# vcf-lm324-stereo.net
KiCad netlist of a schematic drawn in EAGLE
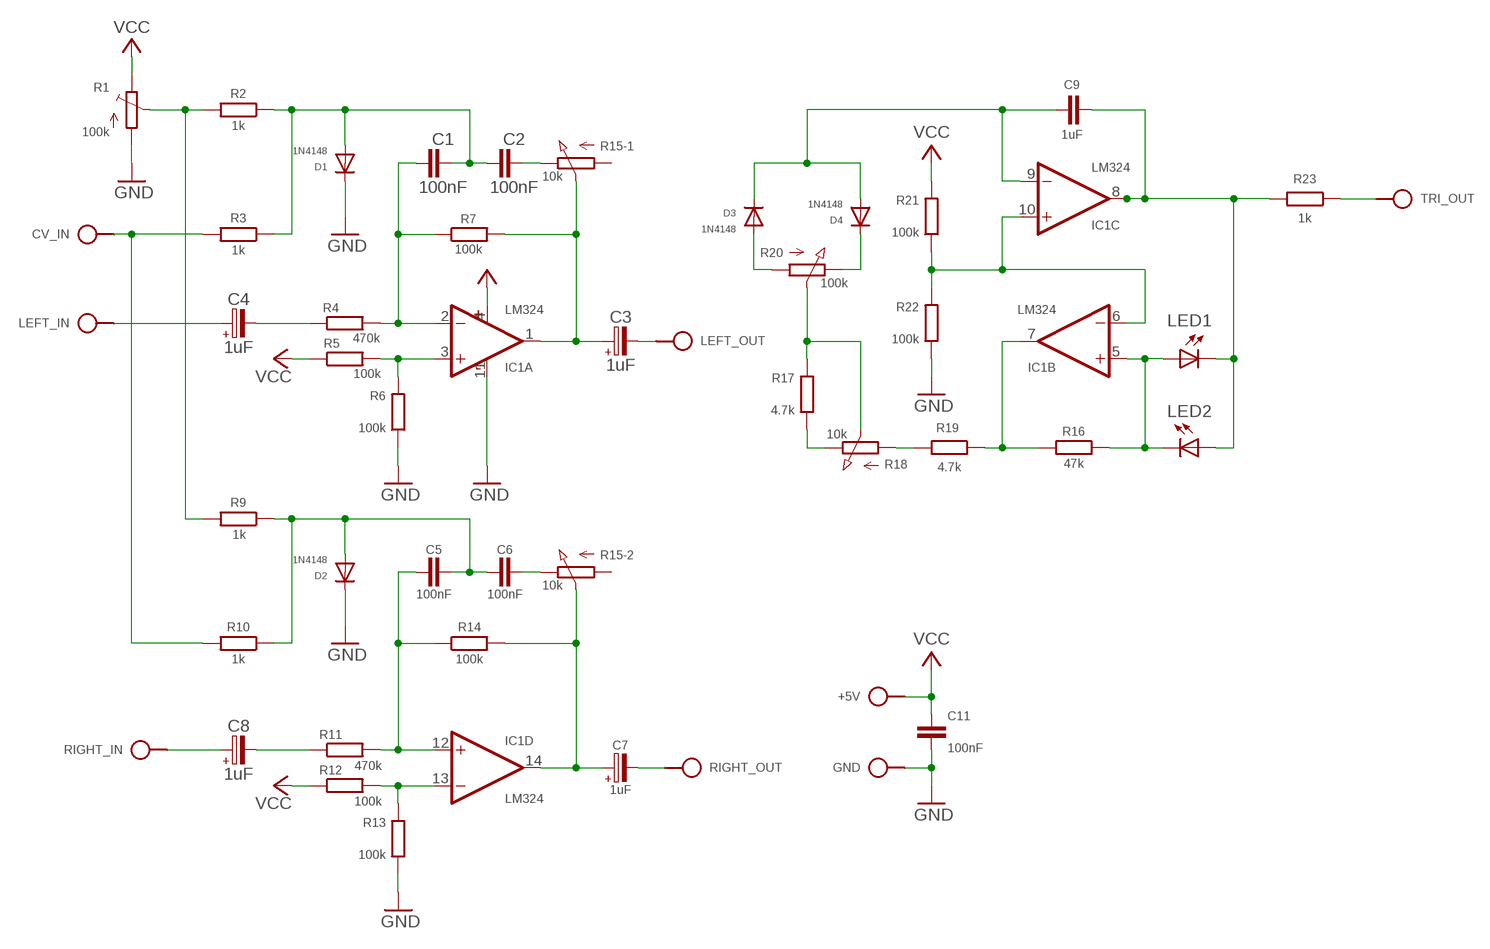
[diagram p0: schematic, sheet 1]

(export (version "E")
  (design (tool "Eeschema 10.0.6"))
  (components
    (comp (ref "+5V")
      (value "VCC")
      (footprint "eagle-import:SPAD")
      (libsource (lib "eagle-import") (part "SPAD"))
    )
    (comp (ref "C1")
      (value "100nF")
      (footprint "eagle-import:C050-024X044")
      (libsource (lib "eagle-import") (part "C050-024X044"))
    )
    (comp (ref "C2")
      (value "100nF")
      (footprint "eagle-import:C050-024X044")
      (libsource (lib "eagle-import") (part "C050-024X044"))
    )
    (comp (ref "C3")
      (value "1uF")
      (footprint "eagle-import:E2,5-3")
      (libsource (lib "eagle-import") (part "CPOLE2,5-3"))
    )
    (comp (ref "C4")
      (value "1uF")
      (footprint "eagle-import:E2,5-3")
      (libsource (lib "eagle-import") (part "CPOLE2,5-3"))
    )
    (comp (ref "C5")
      (value "100nF")
      (footprint "eagle-import:C050-024X044")
      (libsource (lib "eagle-import") (part "C050-024X044"))
    )
    (comp (ref "C6")
      (value "100nF")
      (footprint "eagle-import:C050-024X044")
      (libsource (lib "eagle-import") (part "C050-024X044"))
    )
    (comp (ref "C7")
      (value "1uF")
      (footprint "eagle-import:E2,5-3")
      (libsource (lib "eagle-import") (part "CPOLE2,5-3"))
    )
    (comp (ref "C8")
      (value "1uF")
      (footprint "eagle-import:E2,5-3")
      (libsource (lib "eagle-import") (part "CPOLE2,5-3"))
    )
    (comp (ref "C9")
      (value "1uF")
      (footprint "eagle-import:C050-024X044_V")
      (libsource (lib "eagle-import") (part "C050-024X044/V"))
    )
    (comp (ref "C11")
      (value "100nF")
      (footprint "eagle-import:C050-020X036")
      (libsource (lib "eagle-import") (part "C050-020X036"))
    )
    (comp (ref "CV_IN")
      (value "CV_IN")
      (footprint "eagle-import:SPAD")
      (libsource (lib "eagle-import") (part "SPAD"))
    )
    (comp (ref "D1")
      (value "1N4148")
      (footprint "eagle-import:DO34-10V")
      (libsource (lib "eagle-import") (part "1N414834-10V"))
    )
    (comp (ref "D2")
      (value "1N4148")
      (footprint "eagle-import:DO34-7V")
      (libsource (lib "eagle-import") (part "1N414834-7V"))
    )
    (comp (ref "D3")
      (value "1N4148")
      (footprint "eagle-import:DO34-7V")
      (libsource (lib "eagle-import") (part "1N414834-7V"))
    )
    (comp (ref "D4")
      (value "1N4148")
      (footprint "eagle-import:DO34-7V")
      (libsource (lib "eagle-import") (part "1N414834-7V"))
    )
    (comp (ref "GND")
      (value "GND")
      (footprint "eagle-import:SPAD")
      (libsource (lib "eagle-import") (part "SPAD"))
    )
    (comp (ref "IC1")
      (value "LM324")
      (footprint "eagle-import:DIL14")
      (libsource (lib "eagle-import") (part "LM324N"))
    )
    (comp (ref "LED1")
      (value "LED3MM")
      (footprint "eagle-import:LED3MM")
      (libsource (lib "eagle-import") (part "LED3MM"))
    )
    (comp (ref "LED2")
      (value "LED3MM")
      (footprint "eagle-import:LED3MM")
      (libsource (lib "eagle-import") (part "LED3MM"))
    )
    (comp (ref "LEFT_IN")
      (value "AUDIO_IN")
      (footprint "eagle-import:SPAD")
      (libsource (lib "eagle-import") (part "SPAD"))
    )
    (comp (ref "LEFT_OUT")
      (value "AUDIO_OUT")
      (footprint "eagle-import:SPAD")
      (libsource (lib "eagle-import") (part "SPAD"))
    )
    (comp (ref "R1")
      (value "100k")
      (footprint "eagle-import:B64Y")
      (libsource (lib "eagle-import") (part "TRIM"))
    )
    (comp (ref "R2")
      (value "1k")
      (footprint "eagle-import:0202_7")
      (libsource (lib "eagle-import") (part "R0202/7"))
    )
    (comp (ref "R3")
      (value "1k")
      (footprint "eagle-import:0202_7")
      (libsource (lib "eagle-import") (part "R0202/7"))
    )
    (comp (ref "R4")
      (value "470k")
      (footprint "eagle-import:0202_7")
      (libsource (lib "eagle-import") (part "R0202/7"))
    )
    (comp (ref "R5")
      (value "100k")
      (footprint "eagle-import:0202_7")
      (libsource (lib "eagle-import") (part "R0202/7"))
    )
    (comp (ref "R6")
      (value "100k")
      (footprint "eagle-import:0202_7")
      (libsource (lib "eagle-import") (part "R0202/7"))
    )
    (comp (ref "R7")
      (value "100k")
      (footprint "eagle-import:0202_7")
      (libsource (lib "eagle-import") (part "R0202/7"))
    )
    (comp (ref "R9")
      (value "1k")
      (footprint "eagle-import:0202_7")
      (libsource (lib "eagle-import") (part "R0202/7"))
    )
    (comp (ref "R10")
      (value "1k")
      (footprint "eagle-import:0202_7")
      (libsource (lib "eagle-import") (part "R0202/7"))
    )
    (comp (ref "R11")
      (value "470k")
      (footprint "eagle-import:0202_7")
      (libsource (lib "eagle-import") (part "R0202/7"))
    )
    (comp (ref "R12")
      (value "100k")
      (footprint "eagle-import:0202_7")
      (libsource (lib "eagle-import") (part "R0202/7"))
    )
    (comp (ref "R13")
      (value "100k")
      (footprint "eagle-import:0202_7")
      (libsource (lib "eagle-import") (part "R0202/7"))
    )
    (comp (ref "R14")
      (value "100k")
      (footprint "eagle-import:0202_7")
      (libsource (lib "eagle-import") (part "R0202/7"))
    )
    (comp (ref "R15")
      (value "10k")
      (footprint "eagle-import:POT-STEREO")
      (libsource (lib "eagle-import") (part "POT-STEREO"))
    )
    (comp (ref "R16")
      (value "47k")
      (footprint "eagle-import:0202_7-V")
      (libsource (lib "eagle-import") (part "R0202/7-V"))
    )
    (comp (ref "R17")
      (value "4.7k")
      (footprint "eagle-import:0202_7")
      (libsource (lib "eagle-import") (part "R0202/7"))
    )
    (comp (ref "R18")
      (value "10k")
      (footprint "eagle-import:POT")
      (libsource (lib "eagle-import") (part "POT"))
    )
    (comp (ref "R19")
      (value "4.7k")
      (footprint "eagle-import:0202_7-V")
      (libsource (lib "eagle-import") (part "R0202/7-V"))
    )
    (comp (ref "R20")
      (value "100k")
      (footprint "eagle-import:POT")
      (libsource (lib "eagle-import") (part "POT"))
    )
    (comp (ref "R21")
      (value "100k")
      (footprint "eagle-import:0202_7-V")
      (libsource (lib "eagle-import") (part "R0202/7-V"))
    )
    (comp (ref "R22")
      (value "100k")
      (footprint "eagle-import:0202_7-V")
      (libsource (lib "eagle-import") (part "R0202/7-V"))
    )
    (comp (ref "R23")
      (value "1k")
      (footprint "eagle-import:0202_7-V")
      (libsource (lib "eagle-import") (part "R0202/7-V"))
    )
    (comp (ref "RIGHT_IN")
      (value "AUDIO_IN")
      (footprint "eagle-import:SPAD")
      (libsource (lib "eagle-import") (part "SPAD"))
    )
    (comp (ref "RIGHT_OUT")
      (value "AUDIO_OUT")
      (footprint "eagle-import:SPAD")
      (libsource (lib "eagle-import") (part "SPAD"))
    )
    (comp (ref "TRI_OUT")
      (value "TRIANGLE")
      (footprint "eagle-import:SPAD")
      (libsource (lib "eagle-import") (part "SPAD"))
    )
  )
  (nets
    (net (code "1") (name "GND") (class "Default")
      (node (ref "C11") (pin "2") (pinfunction "2_2") (pintype "passive"))
      (node (ref "D1") (pin "C") (pinfunction "C_C") (pintype "passive"))
      (node (ref "D2") (pin "C") (pinfunction "C_C") (pintype "passive"))
      (node (ref "GND") (pin "1") (pinfunction "P$1_1") (pintype "bidirectional"))
      (node (ref "IC1") (pin "11") (pinfunction "V-_11") (pintype "power_in"))
      (node (ref "R1") (pin "A") (pinfunction "A_A") (pintype "passive"))
      (node (ref "R13") (pin "1") (pinfunction "1_1") (pintype "passive"))
      (node (ref "R22") (pin "1") (pinfunction "1_1") (pintype "passive"))
      (node (ref "R6") (pin "1") (pinfunction "1_1") (pintype "passive"))
    )
    (net (code "2") (name "Net-(C1-Pad2)") (class "Default")
      (node (ref "C1") (pin "2") (pinfunction "2_2") (pintype "passive"))
      (node (ref "C2") (pin "1") (pinfunction "1_1") (pintype "passive"))
      (node (ref "D1") (pin "A") (pinfunction "A_A") (pintype "passive"))
      (node (ref "R2") (pin "1") (pinfunction "1_1") (pintype "passive"))
      (node (ref "R3") (pin "1") (pinfunction "1_1") (pintype "passive"))
    )
    (net (code "3") (name "Net-(C4-Pad-)") (class "Default")
      (node (ref "C4") (pin "-") (pinfunction "-_-") (pintype "passive"))
      (node (ref "R4") (pin "1") (pinfunction "1_1") (pintype "passive"))
    )
    (net (code "4") (name "Net-(C5-Pad2)") (class "Default")
      (node (ref "C5") (pin "2") (pinfunction "2_2") (pintype "passive"))
      (node (ref "C6") (pin "1") (pinfunction "1_1") (pintype "passive"))
      (node (ref "D2") (pin "A") (pinfunction "A_A") (pintype "passive"))
      (node (ref "R10") (pin "1") (pinfunction "1_1") (pintype "passive"))
      (node (ref "R9") (pin "1") (pinfunction "1_1") (pintype "passive"))
    )
    (net (code "5") (name "Net-(C8-Pad-)") (class "Default")
      (node (ref "C8") (pin "-") (pinfunction "-_-") (pintype "passive"))
      (node (ref "R11") (pin "1") (pinfunction "1_1") (pintype "passive"))
    )
    (net (code "6") (name "Net-(CV_IN-P$1)") (class "Default")
      (node (ref "CV_IN") (pin "1") (pinfunction "P$1_1") (pintype "bidirectional"))
      (node (ref "R10") (pin "2") (pinfunction "2_2") (pintype "passive"))
      (node (ref "R3") (pin "2") (pinfunction "2_2") (pintype "passive"))
    )
    (net (code "7") (name "Net-(IC1A-+IN)") (class "Default")
      (node (ref "IC1") (pin "3") (pinfunction "+IN_3") (pintype "input"))
      (node (ref "R5") (pin "2") (pinfunction "2_2") (pintype "passive"))
      (node (ref "R6") (pin "2") (pinfunction "2_2") (pintype "passive"))
    )
    (net (code "8") (name "Net-(IC1A--IN)") (class "Default")
      (node (ref "C1") (pin "1") (pinfunction "1_1") (pintype "passive"))
      (node (ref "IC1") (pin "2") (pinfunction "-IN_2") (pintype "input"))
      (node (ref "R4") (pin "2") (pinfunction "2_2") (pintype "passive"))
      (node (ref "R7") (pin "1") (pinfunction "1_1") (pintype "passive"))
    )
    (net (code "9") (name "Net-(IC1A-OUT)") (class "Default")
      (node (ref "C3") (pin "+") (pinfunction "+_+") (pintype "passive"))
      (node (ref "IC1") (pin "1") (pinfunction "OUT_1") (pintype "output"))
      (node (ref "R15") (pin "1-2") (pinfunction "S_1-2") (pintype "passive"))
      (node (ref "R7") (pin "2") (pinfunction "2_2") (pintype "passive"))
    )
    (net (code "10") (name "Net-(IC1B-+IN)") (class "Default")
      (node (ref "IC1") (pin "5") (pinfunction "+IN_5") (pintype "input"))
      (node (ref "LED1") (pin "A") (pinfunction "A_A") (pintype "passive"))
      (node (ref "LED2") (pin "K") (pinfunction "C_K") (pintype "passive"))
      (node (ref "R16") (pin "1") (pinfunction "1_1") (pintype "passive"))
    )
    (net (code "11") (name "Net-(IC1B--IN)") (class "Default")
      (node (ref "IC1") (pin "10") (pinfunction "+IN_10") (pintype "input"))
      (node (ref "IC1") (pin "6") (pinfunction "-IN_6") (pintype "input"))
      (node (ref "R21") (pin "1") (pinfunction "1_1") (pintype "passive"))
      (node (ref "R22") (pin "2") (pinfunction "2_2") (pintype "passive"))
    )
    (net (code "12") (name "Net-(IC1B-OUT)") (class "Default")
      (node (ref "IC1") (pin "7") (pinfunction "OUT_7") (pintype "output"))
      (node (ref "R16") (pin "2") (pinfunction "2_2") (pintype "passive"))
      (node (ref "R19") (pin "1") (pinfunction "1_1") (pintype "passive"))
    )
    (net (code "13") (name "Net-(IC1C--IN)") (class "Default")
      (node (ref "C9") (pin "1") (pinfunction "1_1") (pintype "passive"))
      (node (ref "D3") (pin "C") (pinfunction "C_C") (pintype "passive"))
      (node (ref "D4") (pin "A") (pinfunction "A_A") (pintype "passive"))
      (node (ref "IC1") (pin "9") (pinfunction "-IN_9") (pintype "input"))
    )
    (net (code "14") (name "Net-(IC1C-OUT)") (class "Default")
      (node (ref "C9") (pin "2") (pinfunction "2_2") (pintype "passive"))
      (node (ref "IC1") (pin "8") (pinfunction "OUT_8") (pintype "output"))
      (node (ref "LED1") (pin "K") (pinfunction "C_K") (pintype "passive"))
      (node (ref "LED2") (pin "A") (pinfunction "A_A") (pintype "passive"))
      (node (ref "R23") (pin "2") (pinfunction "2_2") (pintype "passive"))
    )
    (net (code "15") (name "Net-(IC1D-+IN)") (class "Default")
      (node (ref "C5") (pin "1") (pinfunction "1_1") (pintype "passive"))
      (node (ref "IC1") (pin "12") (pinfunction "+IN_12") (pintype "input"))
      (node (ref "R11") (pin "2") (pinfunction "2_2") (pintype "passive"))
      (node (ref "R14") (pin "1") (pinfunction "1_1") (pintype "passive"))
    )
    (net (code "16") (name "Net-(IC1D--IN)") (class "Default")
      (node (ref "IC1") (pin "13") (pinfunction "-IN_13") (pintype "input"))
      (node (ref "R12") (pin "2") (pinfunction "2_2") (pintype "passive"))
      (node (ref "R13") (pin "2") (pinfunction "2_2") (pintype "passive"))
    )
    (net (code "17") (name "Net-(IC1D-OUT)") (class "Default")
      (node (ref "C7") (pin "+") (pinfunction "+_+") (pintype "passive"))
      (node (ref "IC1") (pin "14") (pinfunction "OUT_14") (pintype "output"))
      (node (ref "R14") (pin "2") (pinfunction "2_2") (pintype "passive"))
      (node (ref "R15") (pin "2-2") (pinfunction "S_2-2") (pintype "passive"))
    )
    (net (code "18") (name "Net-(LEFT_IN-P$1)") (class "Default")
      (node (ref "C4") (pin "+") (pinfunction "+_+") (pintype "passive"))
      (node (ref "LEFT_IN") (pin "1") (pinfunction "P$1_1") (pintype "bidirectional"))
    )
    (net (code "19") (name "Net-(LEFT_OUT-P$1)") (class "Default")
      (node (ref "C3") (pin "-") (pinfunction "-_-") (pintype "passive"))
      (node (ref "LEFT_OUT") (pin "1") (pinfunction "P$1_1") (pintype "bidirectional"))
    )
    (net (code "20") (name "Net-(R1-PadS)") (class "Default")
      (node (ref "R1") (pin "S") (pinfunction "S_S") (pintype "passive"))
      (node (ref "R2") (pin "2") (pinfunction "2_2") (pintype "passive"))
      (node (ref "R9") (pin "2") (pinfunction "2_2") (pintype "passive"))
    )
    (net (code "21") (name "Net-(R15A-E)") (class "Default")
      (node (ref "C2") (pin "2") (pinfunction "2_2") (pintype "passive"))
      (node (ref "R15") (pin "1-3") (pinfunction "E_1-3") (pintype "passive"))
    )
    (net (code "22") (name "Net-(R15B-E)") (class "Default")
      (node (ref "C6") (pin "2") (pinfunction "2_2") (pintype "passive"))
      (node (ref "R15") (pin "2-3") (pinfunction "E_2-3") (pintype "passive"))
    )
    (net (code "23") (name "Net-(R18-A)") (class "Default")
      (node (ref "R18") (pin "1") (pinfunction "A_1") (pintype "passive"))
      (node (ref "R19") (pin "2") (pinfunction "2_2") (pintype "passive"))
    )
    (net (code "24") (name "Net-(R18-E)") (class "Default")
      (node (ref "R17") (pin "1") (pinfunction "1_1") (pintype "passive"))
      (node (ref "R18") (pin "3") (pinfunction "E_3") (pintype "passive"))
    )
    (net (code "25") (name "Net-(R18-S)") (class "Default")
      (node (ref "R17") (pin "2") (pinfunction "2_2") (pintype "passive"))
      (node (ref "R18") (pin "2") (pinfunction "S_2") (pintype "passive"))
      (node (ref "R20") (pin "2") (pinfunction "S_2") (pintype "passive"))
    )
    (net (code "26") (name "Net-(R20-A)") (class "Default")
      (node (ref "D3") (pin "A") (pinfunction "A_A") (pintype "passive"))
      (node (ref "R20") (pin "1") (pinfunction "A_1") (pintype "passive"))
    )
    (net (code "27") (name "Net-(R20-E)") (class "Default")
      (node (ref "D4") (pin "C") (pinfunction "C_C") (pintype "passive"))
      (node (ref "R20") (pin "3") (pinfunction "E_3") (pintype "passive"))
    )
    (net (code "28") (name "Net-(RIGHT_IN-P$1)") (class "Default")
      (node (ref "C8") (pin "+") (pinfunction "+_+") (pintype "passive"))
      (node (ref "RIGHT_IN") (pin "1") (pinfunction "P$1_1") (pintype "bidirectional"))
    )
    (net (code "29") (name "Net-(RIGHT_OUT-P$1)") (class "Default")
      (node (ref "C7") (pin "-") (pinfunction "-_-") (pintype "passive"))
      (node (ref "RIGHT_OUT") (pin "1") (pinfunction "P$1_1") (pintype "bidirectional"))
    )
    (net (code "30") (name "Net-(TRI_OUT-P$1)") (class "Default")
      (node (ref "R23") (pin "1") (pinfunction "1_1") (pintype "passive"))
      (node (ref "TRI_OUT") (pin "1") (pinfunction "P$1_1") (pintype "bidirectional"))
    )
    (net (code "31") (name "VCC") (class "Default")
      (node (ref "+5V") (pin "1") (pinfunction "P$1_1") (pintype "bidirectional"))
      (node (ref "C11") (pin "1") (pinfunction "1_1") (pintype "passive"))
      (node (ref "IC1") (pin "4") (pinfunction "V+_4") (pintype "power_in"))
      (node (ref "R1") (pin "E") (pinfunction "E_E") (pintype "passive"))
      (node (ref "R12") (pin "1") (pinfunction "1_1") (pintype "passive"))
      (node (ref "R21") (pin "2") (pinfunction "2_2") (pintype "passive"))
      (node (ref "R5") (pin "1") (pinfunction "1_1") (pintype "passive"))
    )
    (net (code "32") (name "unconnected-(R15A-A-Pad1-1)") (class "Default")
      (node (ref "R15") (pin "1-1") (pinfunction "A_1-1") (pintype "passive"))
    )
    (net (code "33") (name "unconnected-(R15B-A-Pad2-1)") (class "Default")
      (node (ref "R15") (pin "2-1") (pinfunction "A_2-1") (pintype "passive"))
    )
  )
)
